# wlpkt1_pk.net
KiCad netlist of a schematic drawn in Altium Designer
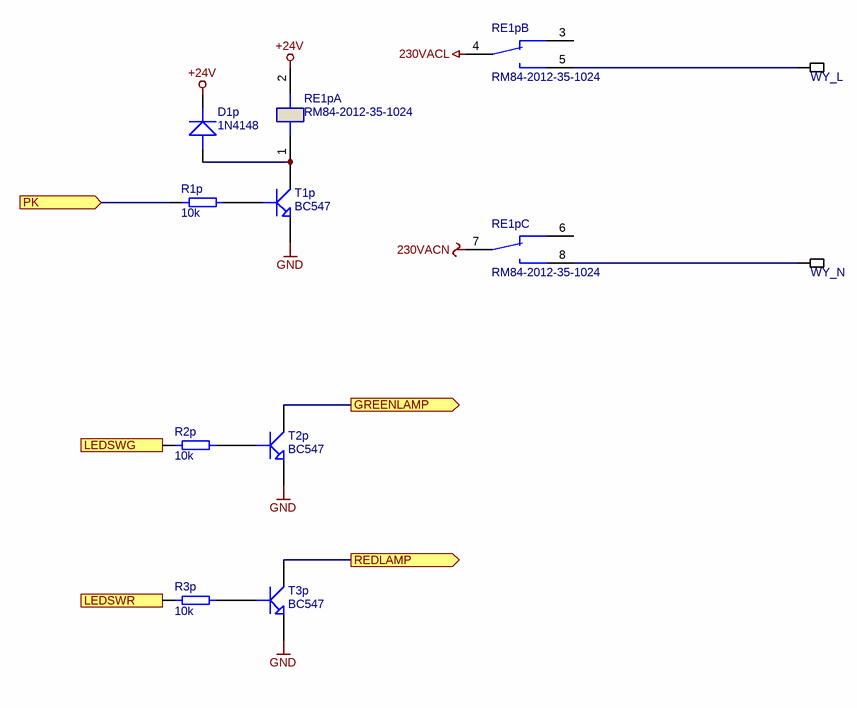
[diagram p0: wlpkt1_pk.SchDoc]

(export (version "E")
  (design (tool "Eeschema 10.0.6"))
  (components
    (comp (ref "D1p") (value "1N4148") (footprint "CE02") (libsource (lib "PartsMySQL") (part "DIODE")))
    (comp (ref "R1p") (value "10k") (footprint "0805R") (libsource (lib "PartsMySQL") (part "R")))
    (comp (ref "R2p") (value "10k") (footprint "0805R") (libsource (lib "PartsMySQL") (part "R")))
    (comp (ref "R3p") (value "10k") (footprint "0805R") (libsource (lib "PartsMySQL") (part "R")))
    (comp (ref "RE1p")
      (value "RM84-2012-35-1024")
      (footprint "RM84-P")
      (libsource (lib "PartsMySQL") (part "RM84-P"))
    )
    (comp (ref "T1p") (value "BC547") (footprint "CE35V4") (libsource (lib "PartsMySQL") (part "NPN_CE35V4")))
    (comp (ref "T2p") (value "BC547") (footprint "CE35V4") (libsource (lib "PartsMySQL") (part "NPN_CE35V4")))
    (comp (ref "T3p") (value "BC547") (footprint "CE35V4") (libsource (lib "PartsMySQL") (part "NPN_CE35V4")))
    (comp (ref "WY_L")
      (value "PAD1_5MM")
      (footprint "PAD1_5MM")
      (libsource (lib "PartsMySQL") (part "CLAMP_NOBOM"))
    )
    (comp (ref "WY_N")
      (value "PAD1_5MM")
      (footprint "PAD1_5MM")
      (libsource (lib "PartsMySQL") (part "CLAMP_NOBOM"))
    )
  )
  (nets
    (net (code "1") (name "+24V") (class "Default")
      (node (ref "D1p") (pin "CATH") (pinfunction "CATH_CATH") (pintype "passive"))
      (node (ref "RE1p") (pin "2") (pinfunction "A2_2") (pintype "passive"))
    )
    (net (code "2") (name "/GREENLAMP") (class "Default")
      (node (ref "T2p") (pin "COLL") (pinfunction "COLL_COLL") (pintype "passive"))
    )
    (net (code "3") (name "/LEDSWG") (class "Default")
      (node (ref "R2p") (pin "2") (pinfunction "2_2") (pintype "passive"))
    )
    (net (code "4") (name "/LEDSWR") (class "Default")
      (node (ref "R3p") (pin "2") (pinfunction "2_2") (pintype "passive"))
    )
    (net (code "5") (name "/PK") (class "Default")
      (node (ref "R1p") (pin "2") (pinfunction "2_2") (pintype "passive"))
    )
    (net (code "6") (name "/REDLAMP") (class "Default")
      (node (ref "T3p") (pin "COLL") (pinfunction "COLL_COLL") (pintype "passive"))
    )
    (net (code "7") (name "230VACL") (class "Default")
      (node (ref "RE1p") (pin "4") (pinfunction "21_4") (pintype "passive"))
    )
    (net (code "8") (name "230VACN") (class "Default")
      (node (ref "RE1p") (pin "7") (pinfunction "11_7") (pintype "passive"))
    )
    (net (code "9") (name "GND") (class "Default")
      (node (ref "T1p") (pin "EMIT") (pinfunction "EMIT_EMIT") (pintype "passive"))
      (node (ref "T2p") (pin "EMIT") (pinfunction "EMIT_EMIT") (pintype "passive"))
      (node (ref "T3p") (pin "EMIT") (pinfunction "EMIT_EMIT") (pintype "passive"))
    )
    (net (code "10") (name "Net-(R1p-Pad1)") (class "Default")
      (node (ref "R1p") (pin "1") (pinfunction "1_1") (pintype "passive"))
      (node (ref "T1p") (pin "BASE") (pinfunction "BASE_BASE") (pintype "passive"))
    )
    (net (code "11") (name "Net-(R2p-Pad1)") (class "Default")
      (node (ref "R2p") (pin "1") (pinfunction "1_1") (pintype "passive"))
      (node (ref "T2p") (pin "BASE") (pinfunction "BASE_BASE") (pintype "passive"))
    )
    (net (code "12") (name "Net-(R3p-Pad1)") (class "Default")
      (node (ref "R3p") (pin "1") (pinfunction "1_1") (pintype "passive"))
      (node (ref "T3p") (pin "BASE") (pinfunction "BASE_BASE") (pintype "passive"))
    )
    (net (code "13") (name "Net-(RE1pA-A1)") (class "Default")
      (node (ref "D1p") (pin "ANOD") (pinfunction "ANOD_ANOD") (pintype "passive"))
      (node (ref "RE1p") (pin "1") (pinfunction "A1_1") (pintype "passive"))
      (node (ref "T1p") (pin "COLL") (pinfunction "COLL_COLL") (pintype "passive"))
    )
    (net (code "14") (name "Net-(RE1pB-24)") (class "Default")
      (node (ref "RE1p") (pin "5") (pinfunction "24_5") (pintype "passive"))
      (node (ref "WY_L") (pin "1") (pinfunction "1_1") (pintype "passive"))
    )
    (net (code "15") (name "Net-(RE1pC-14)") (class "Default")
      (node (ref "RE1p") (pin "8") (pinfunction "14_8") (pintype "passive"))
      (node (ref "WY_N") (pin "1") (pinfunction "1_1") (pintype "passive"))
    )
    (net (code "16") (name "unconnected-(RE1pB-22-Pad3)") (class "Default")
      (node (ref "RE1p") (pin "3") (pinfunction "22_3") (pintype "passive"))
    )
    (net (code "17") (name "unconnected-(RE1pC-12-Pad6)") (class "Default")
      (node (ref "RE1p") (pin "6") (pinfunction "12_6") (pintype "passive"))
    )
  )
)
